# SCH_Moje_PCB_2023-10-24.net
KiCad netlist of a schematic drawn in EasyEDA
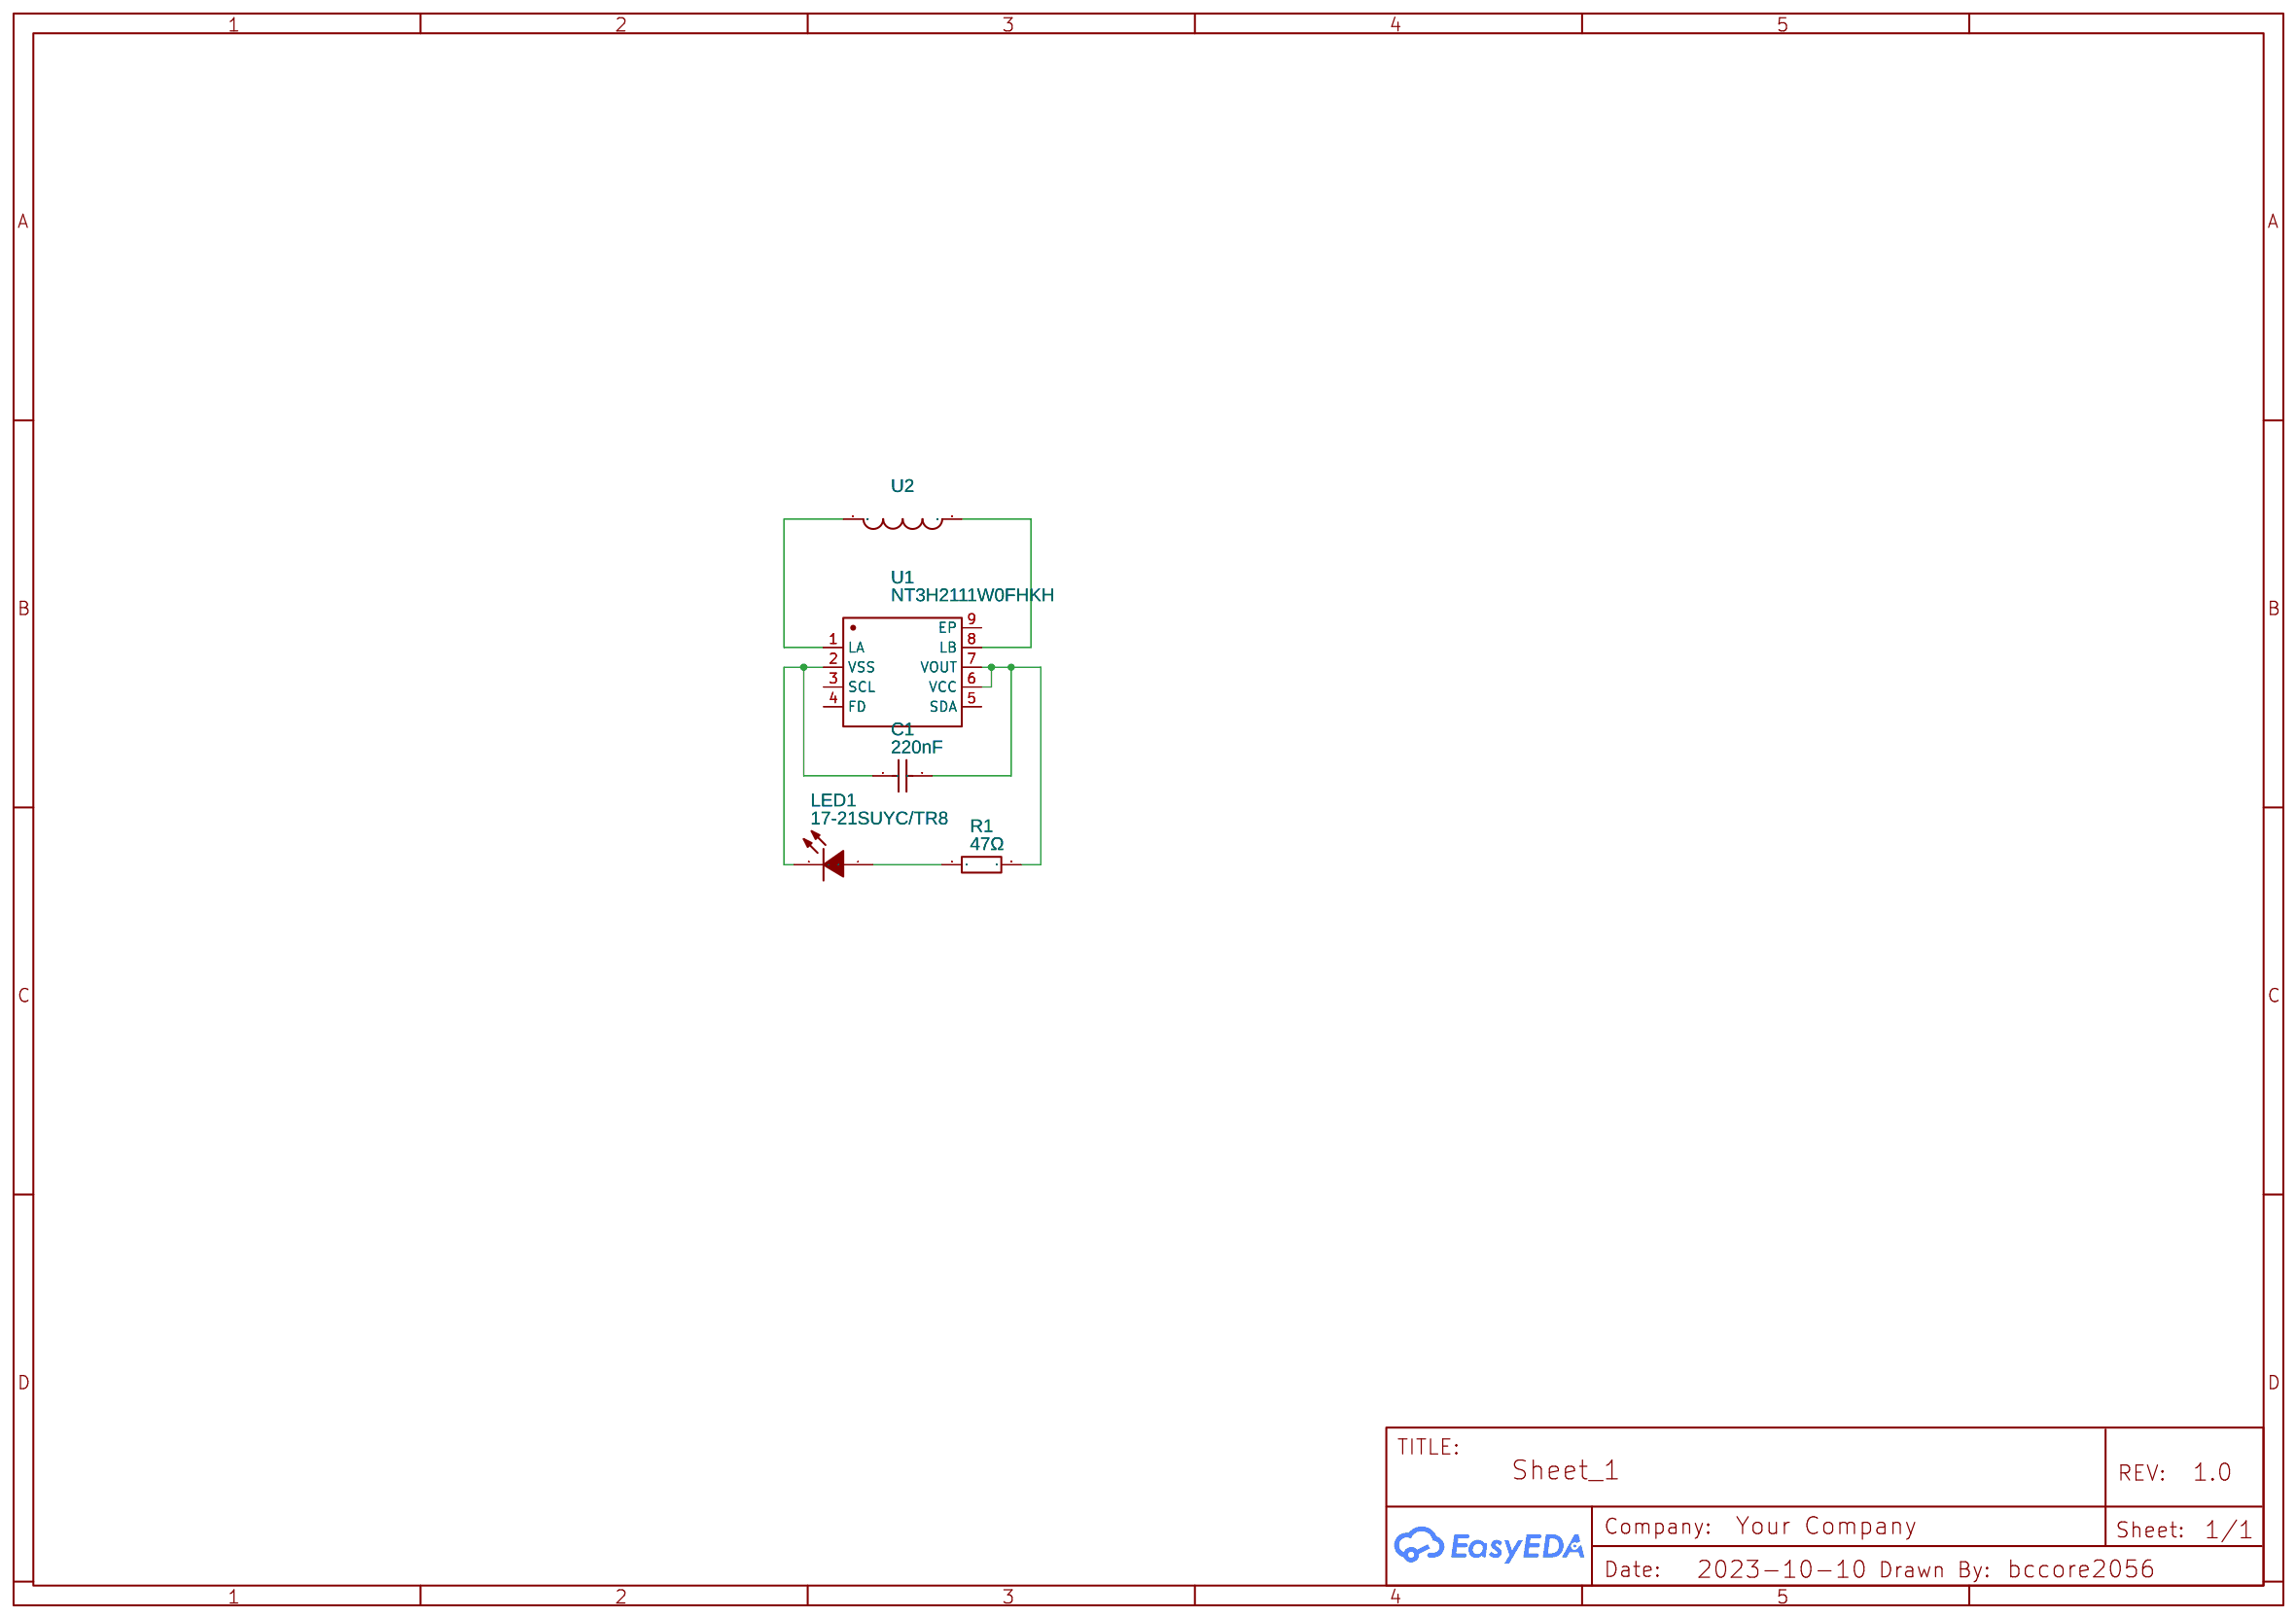
[diagram p0: schematic sheet]

(export (version "E")
  (design (tool "Eeschema 10.0.6"))
  (components
    (comp (ref "C1")
      (value "220nF")
      (fields
        (field (name "Manufacturer Part") "CL10B224KA8NNNC")
        (field (name "Manufacturer") "SAMSUNG(三星)")
      )
      (libsource (lib "") (part "CL10B224KA8NNNC"))
    )
    (comp (ref "LED1")
      (value "17-21SUYC/TR8")
      (fields (field (name "Manufacturer Part") "KT-0805黄灯") (field (name "Manufacturer") "KENTO"))
      (libsource (lib "") (part "17-21SUYC/TR8"))
    )
    (comp (ref "R1")
      (value "47Ω")
      (fields
        (field (name "Manufacturer Part") "0603WAF470JT5E")
        (field (name "Manufacturer") "UNI-ROYAL(厚声)")
      )
      (libsource (lib "") (part "0603WAF470JT5E"))
    )
    (comp (ref "U1")
      (value "NT3H2111W0FHKH")
      (fields (field (name "Manufacturer") "NXP(恩智浦)"))
      (libsource (lib "") (part "NT3H2111W0FHKH"))
    )
    (comp (ref "U2") (value "NO") (libsource (lib "") (part "25X48MM_NFC_ANTENNA")))
  )
  (nets
    (net (code "1") (name "Net-(LED1-+)") (class "Default")
      (node (ref "LED1") (pin "1") (pinfunction "+_1") (pintype "unspecified"))
      (node (ref "R1") (pin "1") (pinfunction "1_1") (pintype "input"))
    )
    (net (code "2") (name "Net-(LED1--)") (class "Default")
      (node (ref "C1") (pin "1") (pinfunction "1_1") (pintype "input"))
      (node (ref "LED1") (pin "2") (pinfunction "-_2") (pintype "unspecified"))
      (node (ref "U1") (pin "2") (pinfunction "VSS_2") (pintype "unspecified"))
    )
    (net (code "3") (name "Net-(U1-LA)") (class "Default")
      (node (ref "U1") (pin "1") (pinfunction "LA_1") (pintype "unspecified"))
      (node (ref "U2") (pin "P$2") (pinfunction "P$2_P$2") (pintype "bidirectional"))
    )
    (net (code "4") (name "Net-(U1-LB)") (class "Default")
      (node (ref "U1") (pin "8") (pinfunction "LB_8") (pintype "unspecified"))
      (node (ref "U2") (pin "P$1") (pinfunction "P$1_P$1") (pintype "bidirectional"))
    )
    (net (code "5") (name "Net-(U1-VCC)") (class "Default")
      (node (ref "C1") (pin "2") (pinfunction "2_2") (pintype "input"))
      (node (ref "R1") (pin "2") (pinfunction "2_2") (pintype "input"))
      (node (ref "U1") (pin "6") (pinfunction "VCC_6") (pintype "unspecified"))
      (node (ref "U1") (pin "7") (pinfunction "VOUT_7") (pintype "unspecified"))
    )
    (net (code "6") (name "unconnected-(U1-EP-Pad9)") (class "Default")
      (node (ref "U1") (pin "9") (pinfunction "EP_9") (pintype "unspecified"))
    )
    (net (code "7") (name "unconnected-(U1-FD-Pad4)") (class "Default")
      (node (ref "U1") (pin "4") (pinfunction "FD_4") (pintype "unspecified"))
    )
    (net (code "8") (name "unconnected-(U1-SCL-Pad3)") (class "Default")
      (node (ref "U1") (pin "3") (pinfunction "SCL_3") (pintype "unspecified"))
    )
    (net (code "9") (name "unconnected-(U1-SDA-Pad5)") (class "Default")
      (node (ref "U1") (pin "5") (pinfunction "SDA_5") (pintype "unspecified"))
    )
  )
)
